# pid.net
KiCad netlist of a schematic drawn in Altium Designer
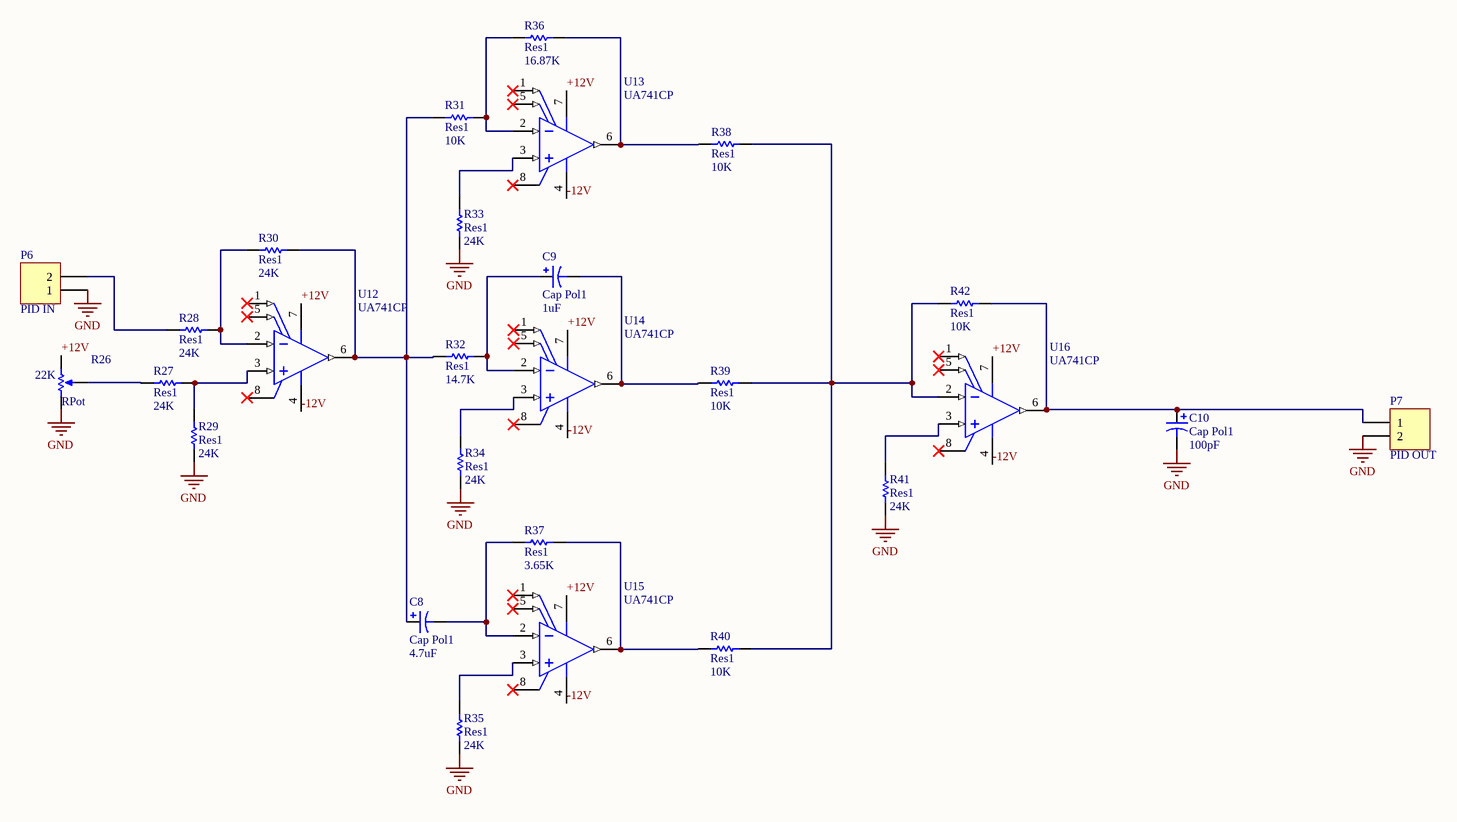
[diagram p0: pid.SchDoc]

(export (version "E")
  (design (tool "Eeschema 10.0.6"))
  (components
    (comp (ref "C8")
      (value "Cap Pol1")
      (footprint "RB7.6-15")
      (description "Polarized Capacitor (Radial)")
      (fields (field (name "ALTIUM_VALUE") "4.7uF") (field (name "PUBLISHER") "Altium Limited"))
      (libsource (lib "Miscellaneous Devices") (part "Cap Pol1"))
    )
    (comp (ref "C9")
      (value "Cap Pol1")
      (footprint "RB7.6-15")
      (description "Polarized Capacitor (Radial)")
      (fields (field (name "ALTIUM_VALUE") "1uF") (field (name "PUBLISHER") "Altium Limited"))
      (libsource (lib "Miscellaneous Devices") (part "Cap Pol1"))
    )
    (comp (ref "C10")
      (value "Cap Pol1")
      (footprint "RB7.6-15")
      (description "Polarized Capacitor (Radial)")
      (fields (field (name "ALTIUM_VALUE") "100pF") (field (name "PUBLISHER") "Altium Limited"))
      (libsource (lib "Miscellaneous Devices") (part "Cap Pol1"))
    )
    (comp (ref "P6")
      (value "PID IN")
      (footprint "HDR1X2")
      (description "Header, 2-Pin")
      (fields (field (name "PUBLISHER") "Altium Limited"))
      (libsource (lib "Miscellaneous Connectors") (part "Header 2"))
    )
    (comp (ref "P7")
      (value "PID OUT")
      (footprint "HDR1X2")
      (description "Header, 2-Pin")
      (fields (field (name "PUBLISHER") "Altium Limited"))
      (libsource (lib "") (part "Header 2_1"))
    )
    (comp (ref "R26")
      (value "RPot")
      (footprint "VR5")
      (description "Potentiometer")
      (fields (field (name "ALTIUM_VALUE") "22K") (field (name "PUBLISHER") "Altium Limited"))
      (libsource (lib "Miscellaneous Devices") (part "RPot"))
    )
    (comp (ref "R27")
      (value "Res1")
      (footprint "AXIAL-0.3")
      (description "Resistor")
      (fields (field (name "ALTIUM_VALUE") "24K") (field (name "PUBLISHER") "Altium Limited"))
      (libsource (lib "Miscellaneous Devices") (part "Res1"))
    )
    (comp (ref "R28")
      (value "Res1")
      (footprint "AXIAL-0.3")
      (description "Resistor")
      (fields (field (name "ALTIUM_VALUE") "24K") (field (name "PUBLISHER") "Altium Limited"))
      (libsource (lib "Miscellaneous Devices") (part "Res1"))
    )
    (comp (ref "R29")
      (value "Res1")
      (footprint "AXIAL-0.3")
      (description "Resistor")
      (fields (field (name "ALTIUM_VALUE") "24K") (field (name "PUBLISHER") "Altium Limited"))
      (libsource (lib "Miscellaneous Devices") (part "Res1"))
    )
    (comp (ref "R30")
      (value "Res1")
      (footprint "AXIAL-0.3")
      (description "Resistor")
      (fields (field (name "ALTIUM_VALUE") "24K") (field (name "PUBLISHER") "Altium Limited"))
      (libsource (lib "Miscellaneous Devices") (part "Res1"))
    )
    (comp (ref "R31")
      (value "Res1")
      (footprint "AXIAL-0.3")
      (description "Resistor")
      (fields (field (name "ALTIUM_VALUE") "10K") (field (name "PUBLISHER") "Altium Limited"))
      (libsource (lib "Miscellaneous Devices") (part "Res1"))
    )
    (comp (ref "R32")
      (value "Res1")
      (footprint "AXIAL-0.3")
      (description "Resistor")
      (fields (field (name "ALTIUM_VALUE") "14.7K") (field (name "PUBLISHER") "Altium Limited"))
      (libsource (lib "Miscellaneous Devices") (part "Res1"))
    )
    (comp (ref "R33")
      (value "Res1")
      (footprint "AXIAL-0.3")
      (description "Resistor")
      (fields (field (name "ALTIUM_VALUE") "24K") (field (name "PUBLISHER") "Altium Limited"))
      (libsource (lib "Miscellaneous Devices") (part "Res1"))
    )
    (comp (ref "R34")
      (value "Res1")
      (footprint "AXIAL-0.3")
      (description "Resistor")
      (fields (field (name "ALTIUM_VALUE") "24K") (field (name "PUBLISHER") "Altium Limited"))
      (libsource (lib "Miscellaneous Devices") (part "Res1"))
    )
    (comp (ref "R35")
      (value "Res1")
      (footprint "AXIAL-0.3")
      (description "Resistor")
      (fields (field (name "ALTIUM_VALUE") "24K") (field (name "PUBLISHER") "Altium Limited"))
      (libsource (lib "Miscellaneous Devices") (part "Res1"))
    )
    (comp (ref "R36")
      (value "Res1")
      (footprint "AXIAL-0.3")
      (description "Resistor")
      (fields (field (name "ALTIUM_VALUE") "16.87K") (field (name "PUBLISHER") "Altium Limited"))
      (libsource (lib "Miscellaneous Devices") (part "Res1"))
    )
    (comp (ref "R37")
      (value "Res1")
      (footprint "AXIAL-0.3")
      (description "Resistor")
      (fields (field (name "ALTIUM_VALUE") "3.65K") (field (name "PUBLISHER") "Altium Limited"))
      (libsource (lib "Miscellaneous Devices") (part "Res1"))
    )
    (comp (ref "R38")
      (value "Res1")
      (footprint "AXIAL-0.3")
      (description "Resistor")
      (fields (field (name "ALTIUM_VALUE") "10K") (field (name "PUBLISHER") "Altium Limited"))
      (libsource (lib "Miscellaneous Devices") (part "Res1"))
    )
    (comp (ref "R39")
      (value "Res1")
      (footprint "AXIAL-0.3")
      (description "Resistor")
      (fields (field (name "ALTIUM_VALUE") "10K") (field (name "PUBLISHER") "Altium Limited"))
      (libsource (lib "Miscellaneous Devices") (part "Res1"))
    )
    (comp (ref "R40")
      (value "Res1")
      (footprint "AXIAL-0.3")
      (description "Resistor")
      (fields (field (name "ALTIUM_VALUE") "10K") (field (name "PUBLISHER") "Altium Limited"))
      (libsource (lib "Miscellaneous Devices") (part "Res1"))
    )
    (comp (ref "R41")
      (value "Res1")
      (footprint "AXIAL-0.3")
      (description "Resistor")
      (fields (field (name "ALTIUM_VALUE") "24K") (field (name "PUBLISHER") "Altium Limited"))
      (libsource (lib "Miscellaneous Devices") (part "Res1"))
    )
    (comp (ref "R42")
      (value "Res1")
      (footprint "AXIAL-0.3")
      (description "Resistor")
      (fields (field (name "ALTIUM_VALUE") "10K") (field (name "PUBLISHER") "Altium Limited"))
      (libsource (lib "Miscellaneous Devices") (part "Res1"))
    )
    (comp (ref "U12")
      (value "UA741CP")
      (footprint "P0008A")
      (description "General-Purpose Operational Amplifier, 7 to 36 V, 0 to 70 degC, 8-pin DIP (P8), Pb-Free (RoHS)")
      (fields (field (name "MANUFACTURER") "Texas Instruments"))
      (libsource (lib "Altium Content Vault") (part "TI-AMP-S5-2-8"))
    )
    (comp (ref "U13")
      (value "UA741CP")
      (footprint "P0008A")
      (description "General-Purpose Operational Amplifier, 7 to 36 V, 0 to 70 degC, 8-pin DIP (P8), Pb-Free (RoHS)")
      (fields (field (name "MANUFACTURER") "Texas Instruments"))
      (libsource (lib "Altium Content Vault") (part "TI-AMP-S5-2-8"))
    )
    (comp (ref "U14")
      (value "UA741CP")
      (footprint "P0008A")
      (description "General-Purpose Operational Amplifier, 7 to 36 V, 0 to 70 degC, 8-pin DIP (P8), Pb-Free (RoHS)")
      (fields (field (name "MANUFACTURER") "Texas Instruments"))
      (libsource (lib "Altium Content Vault") (part "TI-AMP-S5-2-8"))
    )
    (comp (ref "U15")
      (value "UA741CP")
      (footprint "P0008A")
      (description "General-Purpose Operational Amplifier, 7 to 36 V, 0 to 70 degC, 8-pin DIP (P8), Pb-Free (RoHS)")
      (fields (field (name "MANUFACTURER") "Texas Instruments"))
      (libsource (lib "Altium Content Vault") (part "TI-AMP-S5-2-8"))
    )
    (comp (ref "U16")
      (value "UA741CP")
      (footprint "P0008A")
      (description "General-Purpose Operational Amplifier, 7 to 36 V, 0 to 70 degC, 8-pin DIP (P8), Pb-Free (RoHS)")
      (fields (field (name "MANUFACTURER") "Texas Instruments"))
      (libsource (lib "Altium Content Vault") (part "TI-AMP-S5-2-8"))
    )
  )
  (nets
    (net (code "1") (name "/+12V") (class "Default")
      (node (ref "R26") (pin "2") (pinfunction "BOT_2") (pintype "passive"))
      (node (ref "U12") (pin "7") (pinfunction "VCC+_7") (pintype "power_in"))
      (node (ref "U13") (pin "7") (pinfunction "VCC+_7") (pintype "power_in"))
      (node (ref "U14") (pin "7") (pinfunction "VCC+_7") (pintype "power_in"))
      (node (ref "U15") (pin "7") (pinfunction "VCC+_7") (pintype "power_in"))
      (node (ref "U16") (pin "7") (pinfunction "VCC+_7") (pintype "power_in"))
    )
    (net (code "2") (name "/-12V") (class "Default")
      (node (ref "U12") (pin "4") (pinfunction "VCC-_4") (pintype "power_in"))
      (node (ref "U13") (pin "4") (pinfunction "VCC-_4") (pintype "power_in"))
      (node (ref "U14") (pin "4") (pinfunction "VCC-_4") (pintype "power_in"))
      (node (ref "U15") (pin "4") (pinfunction "VCC-_4") (pintype "power_in"))
      (node (ref "U16") (pin "4") (pinfunction "VCC-_4") (pintype "power_in"))
    )
    (net (code "3") (name "GND") (class "Default")
      (node (ref "C10") (pin "2") (pinfunction "2_2") (pintype "passive"))
      (node (ref "P6") (pin "1") (pinfunction "1_1") (pintype "passive"))
      (node (ref "P7") (pin "2") (pinfunction "2_2") (pintype "passive"))
      (node (ref "R26") (pin "1") (pinfunction "TOP_1") (pintype "passive"))
      (node (ref "R29") (pin "2") (pinfunction "2_2") (pintype "passive"))
      (node (ref "R33") (pin "2") (pinfunction "2_2") (pintype "passive"))
      (node (ref "R34") (pin "2") (pinfunction "2_2") (pintype "passive"))
      (node (ref "R35") (pin "2") (pinfunction "2_2") (pintype "passive"))
      (node (ref "R41") (pin "2") (pinfunction "2_2") (pintype "passive"))
    )
    (net (code "4") (name "Net-(P6-Pad2)") (class "Default")
      (node (ref "P6") (pin "2") (pinfunction "2_2") (pintype "passive"))
      (node (ref "R28") (pin "2") (pinfunction "2_2") (pintype "passive"))
    )
    (net (code "5") (name "Net-(R26-TAP)") (class "Default")
      (node (ref "R26") (pin "3") (pinfunction "TAP_3") (pintype "passive"))
      (node (ref "R27") (pin "2") (pinfunction "2_2") (pintype "passive"))
    )
    (net (code "6") (name "Net-(U12-IN+)") (class "Default")
      (node (ref "R27") (pin "1") (pinfunction "1_1") (pintype "passive"))
      (node (ref "R29") (pin "1") (pinfunction "1_1") (pintype "passive"))
      (node (ref "U12") (pin "3") (pinfunction "IN+_3") (pintype "input"))
    )
    (net (code "7") (name "Net-(U12-IN-)") (class "Default")
      (node (ref "R28") (pin "1") (pinfunction "1_1") (pintype "passive"))
      (node (ref "R30") (pin "2") (pinfunction "2_2") (pintype "passive"))
      (node (ref "U12") (pin "2") (pinfunction "IN-_2") (pintype "input"))
    )
    (net (code "8") (name "Net-(U12-OUT)") (class "Default")
      (node (ref "C8") (pin "1") (pinfunction "1_1") (pintype "passive"))
      (node (ref "R30") (pin "1") (pinfunction "1_1") (pintype "passive"))
      (node (ref "R31") (pin "2") (pinfunction "2_2") (pintype "passive"))
      (node (ref "R32") (pin "2") (pinfunction "2_2") (pintype "passive"))
      (node (ref "U12") (pin "6") (pinfunction "OUT_6") (pintype "output"))
    )
    (net (code "9") (name "Net-(U13-IN+)") (class "Default")
      (node (ref "R33") (pin "1") (pinfunction "1_1") (pintype "passive"))
      (node (ref "U13") (pin "3") (pinfunction "IN+_3") (pintype "input"))
    )
    (net (code "10") (name "Net-(U13-IN-)") (class "Default")
      (node (ref "R31") (pin "1") (pinfunction "1_1") (pintype "passive"))
      (node (ref "R36") (pin "2") (pinfunction "2_2") (pintype "passive"))
      (node (ref "U13") (pin "2") (pinfunction "IN-_2") (pintype "input"))
    )
    (net (code "11") (name "Net-(U13-OUT)") (class "Default")
      (node (ref "R36") (pin "1") (pinfunction "1_1") (pintype "passive"))
      (node (ref "R38") (pin "2") (pinfunction "2_2") (pintype "passive"))
      (node (ref "U13") (pin "6") (pinfunction "OUT_6") (pintype "output"))
    )
    (net (code "12") (name "Net-(U14-IN+)") (class "Default")
      (node (ref "R34") (pin "1") (pinfunction "1_1") (pintype "passive"))
      (node (ref "U14") (pin "3") (pinfunction "IN+_3") (pintype "input"))
    )
    (net (code "13") (name "Net-(U14-IN-)") (class "Default")
      (node (ref "C9") (pin "1") (pinfunction "1_1") (pintype "passive"))
      (node (ref "R32") (pin "1") (pinfunction "1_1") (pintype "passive"))
      (node (ref "U14") (pin "2") (pinfunction "IN-_2") (pintype "input"))
    )
    (net (code "14") (name "Net-(U14-OUT)") (class "Default")
      (node (ref "C9") (pin "2") (pinfunction "2_2") (pintype "passive"))
      (node (ref "R39") (pin "2") (pinfunction "2_2") (pintype "passive"))
      (node (ref "U14") (pin "6") (pinfunction "OUT_6") (pintype "output"))
    )
    (net (code "15") (name "Net-(U15-IN+)") (class "Default")
      (node (ref "R35") (pin "1") (pinfunction "1_1") (pintype "passive"))
      (node (ref "U15") (pin "3") (pinfunction "IN+_3") (pintype "input"))
    )
    (net (code "16") (name "Net-(U15-IN-)") (class "Default")
      (node (ref "C8") (pin "2") (pinfunction "2_2") (pintype "passive"))
      (node (ref "R37") (pin "2") (pinfunction "2_2") (pintype "passive"))
      (node (ref "U15") (pin "2") (pinfunction "IN-_2") (pintype "input"))
    )
    (net (code "17") (name "Net-(U15-OUT)") (class "Default")
      (node (ref "R37") (pin "1") (pinfunction "1_1") (pintype "passive"))
      (node (ref "R40") (pin "2") (pinfunction "2_2") (pintype "passive"))
      (node (ref "U15") (pin "6") (pinfunction "OUT_6") (pintype "output"))
    )
    (net (code "18") (name "Net-(U16-IN+)") (class "Default")
      (node (ref "R41") (pin "1") (pinfunction "1_1") (pintype "passive"))
      (node (ref "U16") (pin "3") (pinfunction "IN+_3") (pintype "input"))
    )
    (net (code "19") (name "Net-(U16-IN-)") (class "Default")
      (node (ref "R38") (pin "1") (pinfunction "1_1") (pintype "passive"))
      (node (ref "R39") (pin "1") (pinfunction "1_1") (pintype "passive"))
      (node (ref "R40") (pin "1") (pinfunction "1_1") (pintype "passive"))
      (node (ref "R42") (pin "2") (pinfunction "2_2") (pintype "passive"))
      (node (ref "U16") (pin "2") (pinfunction "IN-_2") (pintype "input"))
    )
    (net (code "20") (name "Net-(U16-OUT)") (class "Default")
      (node (ref "C10") (pin "1") (pinfunction "1_1") (pintype "passive"))
      (node (ref "P7") (pin "1") (pinfunction "1_1") (pintype "passive"))
      (node (ref "R42") (pin "1") (pinfunction "1_1") (pintype "passive"))
      (node (ref "U16") (pin "6") (pinfunction "OUT_6") (pintype "output"))
    )
    (net (code "21") (name "unconnected-(U12-NC-Pad8)") (class "Default")
      (node (ref "U12") (pin "8") (pinfunction "NC_8") (pintype "passive+no_connect"))
    )
    (net (code "22") (name "unconnected-(U12-OFFSET_N1-Pad1)") (class "Default")
      (node (ref "U12") (pin "1") (pinfunction "OFFSET_N1_1") (pintype "input+no_connect"))
    )
    (net (code "23") (name "unconnected-(U12-OFFSET_N2-Pad5)") (class "Default")
      (node (ref "U12") (pin "5") (pinfunction "OFFSET_N2_5") (pintype "input+no_connect"))
    )
    (net (code "24") (name "unconnected-(U13-NC-Pad8)") (class "Default")
      (node (ref "U13") (pin "8") (pinfunction "NC_8") (pintype "passive+no_connect"))
    )
    (net (code "25") (name "unconnected-(U13-OFFSET_N1-Pad1)") (class "Default")
      (node (ref "U13") (pin "1") (pinfunction "OFFSET_N1_1") (pintype "input+no_connect"))
    )
    (net (code "26") (name "unconnected-(U13-OFFSET_N2-Pad5)") (class "Default")
      (node (ref "U13") (pin "5") (pinfunction "OFFSET_N2_5") (pintype "input+no_connect"))
    )
    (net (code "27") (name "unconnected-(U14-NC-Pad8)") (class "Default")
      (node (ref "U14") (pin "8") (pinfunction "NC_8") (pintype "passive+no_connect"))
    )
    (net (code "28") (name "unconnected-(U14-OFFSET_N1-Pad1)") (class "Default")
      (node (ref "U14") (pin "1") (pinfunction "OFFSET_N1_1") (pintype "input+no_connect"))
    )
    (net (code "29") (name "unconnected-(U14-OFFSET_N2-Pad5)") (class "Default")
      (node (ref "U14") (pin "5") (pinfunction "OFFSET_N2_5") (pintype "input+no_connect"))
    )
    (net (code "30") (name "unconnected-(U15-NC-Pad8)") (class "Default")
      (node (ref "U15") (pin "8") (pinfunction "NC_8") (pintype "passive+no_connect"))
    )
    (net (code "31") (name "unconnected-(U15-OFFSET_N1-Pad1)") (class "Default")
      (node (ref "U15") (pin "1") (pinfunction "OFFSET_N1_1") (pintype "input+no_connect"))
    )
    (net (code "32") (name "unconnected-(U15-OFFSET_N2-Pad5)") (class "Default")
      (node (ref "U15") (pin "5") (pinfunction "OFFSET_N2_5") (pintype "input+no_connect"))
    )
    (net (code "33") (name "unconnected-(U16-NC-Pad8)") (class "Default")
      (node (ref "U16") (pin "8") (pinfunction "NC_8") (pintype "passive+no_connect"))
    )
    (net (code "34") (name "unconnected-(U16-OFFSET_N1-Pad1)") (class "Default")
      (node (ref "U16") (pin "1") (pinfunction "OFFSET_N1_1") (pintype "input+no_connect"))
    )
    (net (code "35") (name "unconnected-(U16-OFFSET_N2-Pad5)") (class "Default")
      (node (ref "U16") (pin "5") (pinfunction "OFFSET_N2_5") (pintype "input+no_connect"))
    )
  )
)
